# esquematico.net
KiCad netlist of a schematic drawn in EAGLE
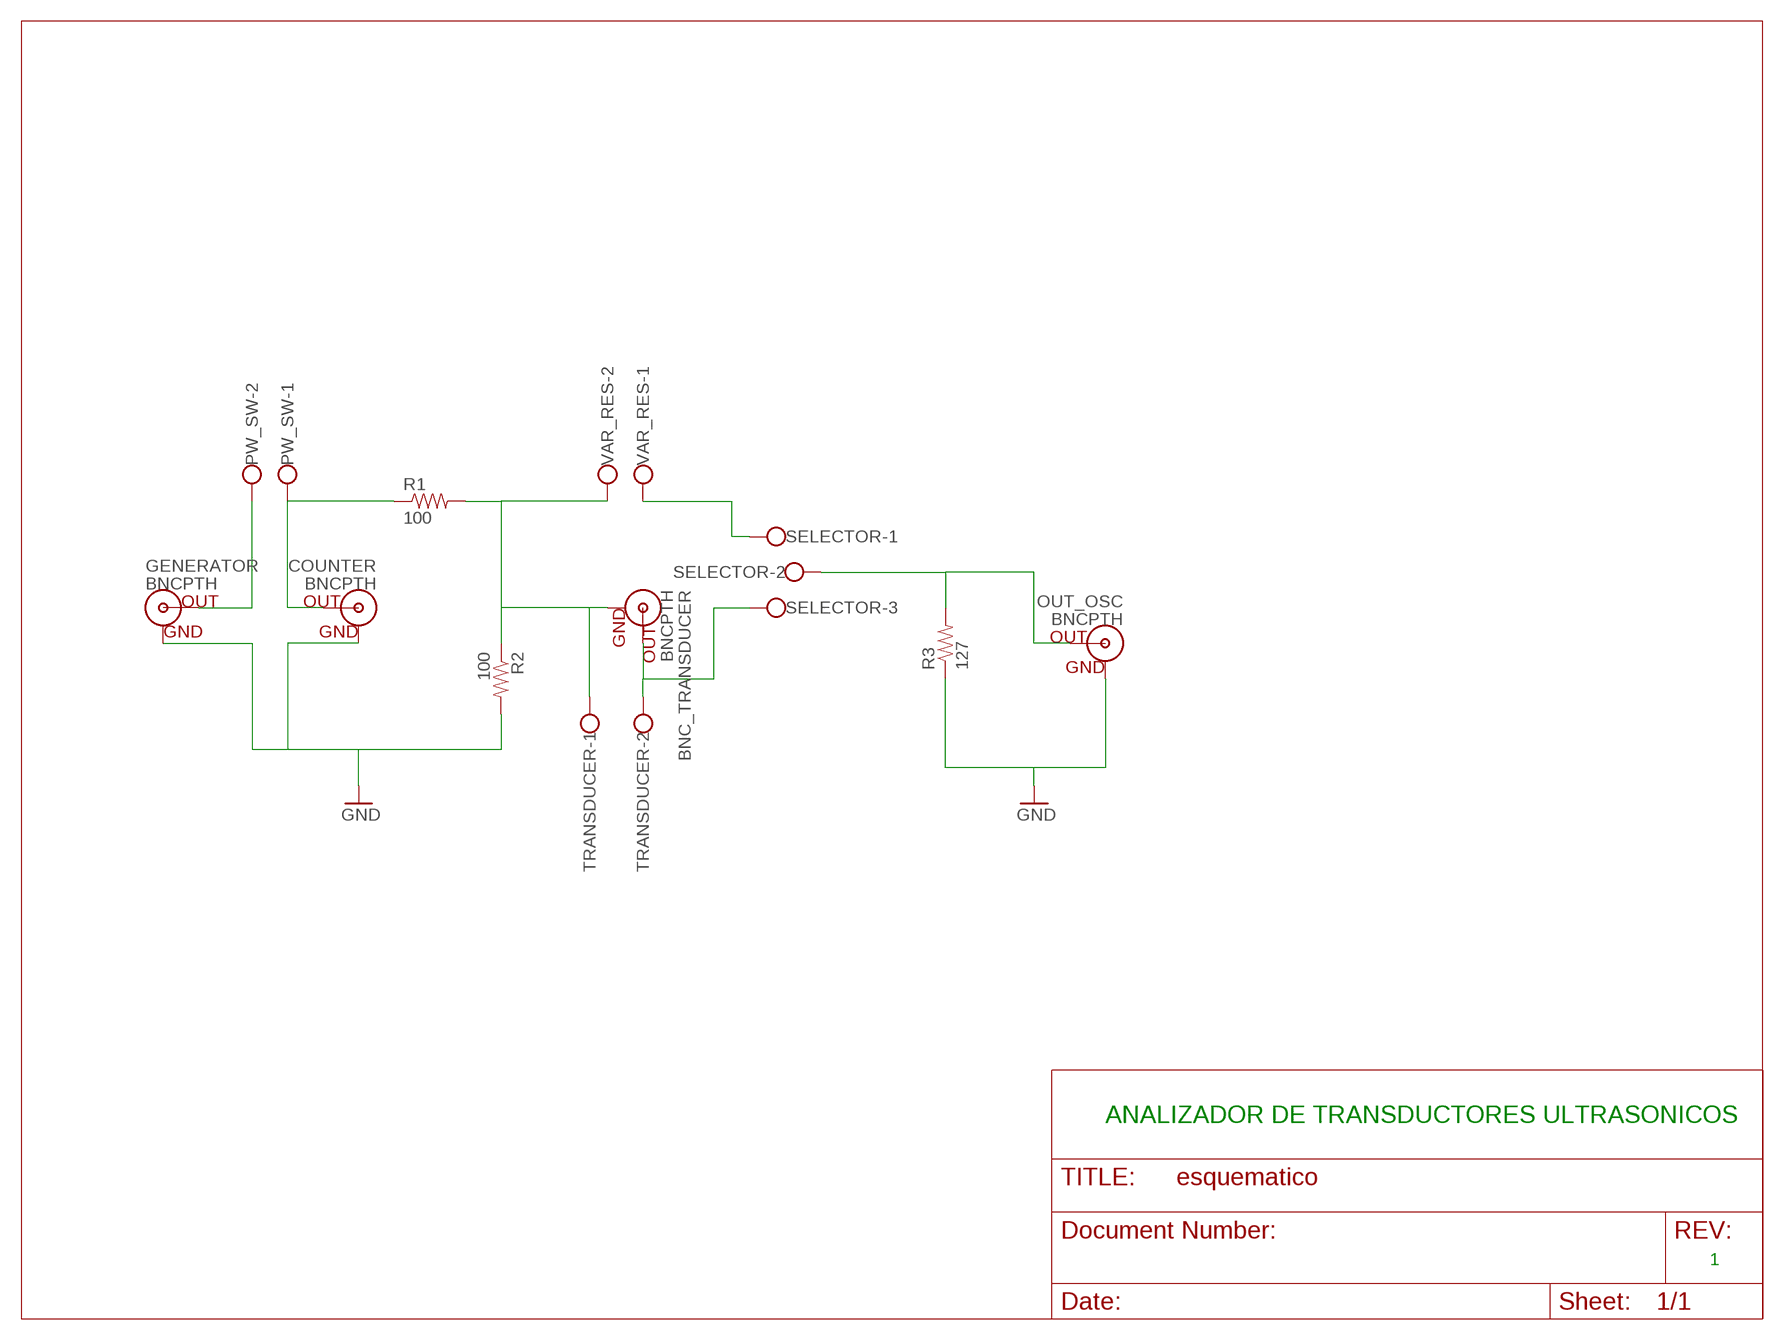
[diagram p0: schematic, sheet 1]

(export (version "E")
  (design (tool "Eeschema 10.0.6"))
  (components
    (comp (ref "BNC_TRANSDUCER")
      (value "BNCPTH")
      (footprint "eagle-import:BNC")
      (libsource (lib "eagle-import") (part "BNCPTH"))
    )
    (comp (ref "COUNTER")
      (value "BNCPTH")
      (footprint "eagle-import:BNC")
      (libsource (lib "eagle-import") (part "BNCPTH"))
    )
    (comp (ref "GENERATOR")
      (value "BNCPTH")
      (footprint "eagle-import:BNC")
      (libsource (lib "eagle-import") (part "BNCPTH"))
    )
    (comp (ref "OUT_OSC")
      (value "BNCPTH")
      (footprint "eagle-import:BNC")
      (libsource (lib "eagle-import") (part "BNCPTH"))
    )
    (comp (ref "PW_SW")
      (value "W237-102")
      (footprint "eagle-import:W237-102")
      (fields (field (name "MPN") "237-102"))
      (libsource (lib "eagle-import") (part "W237-102"))
    )
    (comp (ref "R1")
      (value "100")
      (footprint "eagle-import:AXIAL-0.4")
      (libsource (lib "eagle-import") (part "RESISTORPTH-1/4W"))
    )
    (comp (ref "R2")
      (value "100")
      (footprint "eagle-import:AXIAL-0.4")
      (libsource (lib "eagle-import") (part "RESISTORPTH-1/4W"))
    )
    (comp (ref "R3")
      (value "127")
      (footprint "eagle-import:AXIAL-0.4")
      (libsource (lib "eagle-import") (part "RESISTORPTH-1/4W"))
    )
    (comp (ref "SELECTOR")
      (value "W237-103")
      (footprint "eagle-import:W237-103")
      (fields (field (name "MPN") "237-103"))
      (libsource (lib "eagle-import") (part "W237-103"))
    )
    (comp (ref "TRANSDUCER")
      (value "W237-102")
      (footprint "eagle-import:W237-102")
      (fields (field (name "MPN") "237-102"))
      (libsource (lib "eagle-import") (part "W237-102"))
    )
    (comp (ref "VAR_RES")
      (value "W237-102")
      (footprint "eagle-import:W237-102")
      (fields (field (name "MPN") "237-102"))
      (libsource (lib "eagle-import") (part "W237-102"))
    )
  )
  (nets
    (net (code "1") (name "GND") (class "Default")
      (node (ref "COUNTER") (pin "GND") (pinfunction "GND_GND") (pintype "bidirectional"))
      (node (ref "GENERATOR") (pin "GND") (pinfunction "GND_GND") (pintype "bidirectional"))
      (node (ref "OUT_OSC") (pin "GND") (pinfunction "GND_GND") (pintype "bidirectional"))
      (node (ref "R2") (pin "P$2") (pinfunction "2_P$2") (pintype "passive"))
      (node (ref "R3") (pin "P$1") (pinfunction "1_P$1") (pintype "passive"))
    )
    (net (code "2") (name "Net-(BNC_TRANSDUCER-OUT)") (class "Default")
      (node (ref "BNC_TRANSDUCER") (pin "S") (pinfunction "OUT_S") (pintype "bidirectional"))
      (node (ref "SELECTOR") (pin "3") (pinfunction "KL_3") (pintype "passive"))
      (node (ref "TRANSDUCER") (pin "2") (pinfunction "KL_2") (pintype "passive"))
    )
    (net (code "3") (name "Net-(COUNTER-OUT)") (class "Default")
      (node (ref "COUNTER") (pin "S") (pinfunction "OUT_S") (pintype "bidirectional"))
      (node (ref "PW_SW") (pin "1") (pinfunction "KL_1") (pintype "passive"))
      (node (ref "R1") (pin "P$1") (pinfunction "1_P$1") (pintype "passive"))
    )
    (net (code "4") (name "Net-(GENERATOR-OUT)") (class "Default")
      (node (ref "GENERATOR") (pin "S") (pinfunction "OUT_S") (pintype "bidirectional"))
      (node (ref "PW_SW") (pin "2") (pinfunction "KL_2") (pintype "passive"))
    )
    (net (code "5") (name "Net-(OUT_OSC-OUT)") (class "Default")
      (node (ref "OUT_OSC") (pin "S") (pinfunction "OUT_S") (pintype "bidirectional"))
      (node (ref "R3") (pin "P$2") (pinfunction "2_P$2") (pintype "passive"))
      (node (ref "SELECTOR") (pin "2") (pinfunction "KL_2") (pintype "passive"))
    )
    (net (code "6") (name "Net-(R1-2)") (class "Default")
      (node (ref "BNC_TRANSDUCER") (pin "GND") (pinfunction "GND_GND") (pintype "bidirectional"))
      (node (ref "R1") (pin "P$2") (pinfunction "2_P$2") (pintype "passive"))
      (node (ref "R2") (pin "P$1") (pinfunction "1_P$1") (pintype "passive"))
      (node (ref "TRANSDUCER") (pin "1") (pinfunction "KL_1") (pintype "passive"))
      (node (ref "VAR_RES") (pin "2") (pinfunction "KL_2") (pintype "passive"))
    )
    (net (code "7") (name "Net-(SELECTORA-KL)") (class "Default")
      (node (ref "SELECTOR") (pin "1") (pinfunction "KL_1") (pintype "passive"))
      (node (ref "VAR_RES") (pin "1") (pinfunction "KL_1") (pintype "passive"))
    )
  )
)
